# Sheet1.net
KiCad netlist of a schematic drawn in Altium Designer
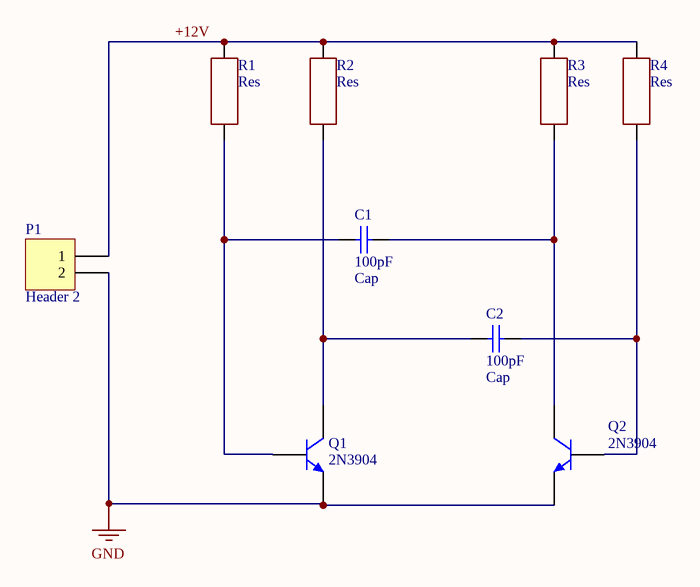
[diagram p0: Sheet1.SchDoc]

(export (version "E")
  (design (tool "Eeschema 10.0.6"))
  (components
    (comp (ref "C1")
      (value "Cap")
      (footprint "RAD-0.3")
      (description "Capacitor")
      (fields (field (name "ALTIUM_VALUE") "100pF") (field (name "PUBLISHER") "Altium Limited"))
      (libsource (lib "Miscellaneous Devices") (part "Cap"))
    )
    (comp (ref "C2")
      (value "Cap")
      (footprint "RAD-0.3")
      (description "Capacitor")
      (fields (field (name "ALTIUM_VALUE") "100pF") (field (name "PUBLISHER") "Altium Limited"))
      (libsource (lib "Miscellaneous Devices") (part "Cap"))
    )
    (comp (ref "P1")
      (value "Header 2")
      (footprint "HDR1X2")
      (description "Header, 2-Pin")
      (fields (field (name "PUBLISHER") "Altium Limited"))
      (libsource (lib "Miscellaneous Connectors") (part "Header 2"))
    )
    (comp (ref "Q1")
      (value "2N3904")
      (footprint "TO-92A")
      (description "NPN General Purpose Amplifier")
      (fields (field (name "PUBLISHER") "Altium Limited"))
      (libsource (lib "Miscellaneous Devices") (part "2N3904"))
    )
    (comp (ref "Q2")
      (value "2N3904")
      (footprint "TO-92A")
      (description "NPN General Purpose Amplifier")
      (fields (field (name "PUBLISHER") "Altium Limited"))
      (libsource (lib "Miscellaneous Devices") (part "2N3904"))
    )
    (comp (ref "R1") (value "Res") (footprint "Res 0805") (libsource (lib "Schlib1") (part "Res")))
    (comp (ref "R2") (value "Res") (footprint "Res 0805") (libsource (lib "Schlib1") (part "Res")))
    (comp (ref "R3") (value "Res") (footprint "Res 0805") (libsource (lib "Schlib1") (part "Res")))
    (comp (ref "R4") (value "Res") (footprint "Res 0805") (libsource (lib "Schlib1") (part "Res")))
  )
  (nets
    (net (code "1") (name "/+12V") (class "Default")
      (node (ref "P1") (pin "1") (pinfunction "1_1") (pintype "passive"))
      (node (ref "R1") (pin "2") (pinfunction "2_2") (pintype "passive"))
      (node (ref "R2") (pin "2") (pinfunction "2_2") (pintype "passive"))
      (node (ref "R3") (pin "2") (pinfunction "2_2") (pintype "passive"))
      (node (ref "R4") (pin "2") (pinfunction "2_2") (pintype "passive"))
    )
    (net (code "2") (name "GND") (class "Default")
      (node (ref "P1") (pin "2") (pinfunction "2_2") (pintype "passive"))
      (node (ref "Q1") (pin "1") (pinfunction "E_1") (pintype "passive"))
      (node (ref "Q2") (pin "1") (pinfunction "E_1") (pintype "passive"))
    )
    (net (code "3") (name "Net-(Q1-B)") (class "Default")
      (node (ref "C1") (pin "1") (pinfunction "1_1") (pintype "passive"))
      (node (ref "Q1") (pin "2") (pinfunction "B_2") (pintype "passive"))
      (node (ref "R1") (pin "1") (pinfunction "1_1") (pintype "passive"))
    )
    (net (code "4") (name "Net-(Q1-C)") (class "Default")
      (node (ref "C2") (pin "1") (pinfunction "1_1") (pintype "passive"))
      (node (ref "Q1") (pin "3") (pinfunction "C_3") (pintype "passive"))
      (node (ref "R2") (pin "1") (pinfunction "1_1") (pintype "passive"))
    )
    (net (code "5") (name "Net-(Q2-B)") (class "Default")
      (node (ref "C2") (pin "2") (pinfunction "2_2") (pintype "passive"))
      (node (ref "Q2") (pin "2") (pinfunction "B_2") (pintype "passive"))
      (node (ref "R4") (pin "1") (pinfunction "1_1") (pintype "passive"))
    )
    (net (code "6") (name "Net-(Q2-C)") (class "Default")
      (node (ref "C1") (pin "2") (pinfunction "2_2") (pintype "passive"))
      (node (ref "Q2") (pin "3") (pinfunction "C_3") (pintype "passive"))
      (node (ref "R3") (pin "1") (pinfunction "1_1") (pintype "passive"))
    )
  )
)
